# heater_controller.net
KiCad netlist of a schematic drawn in EAGLE
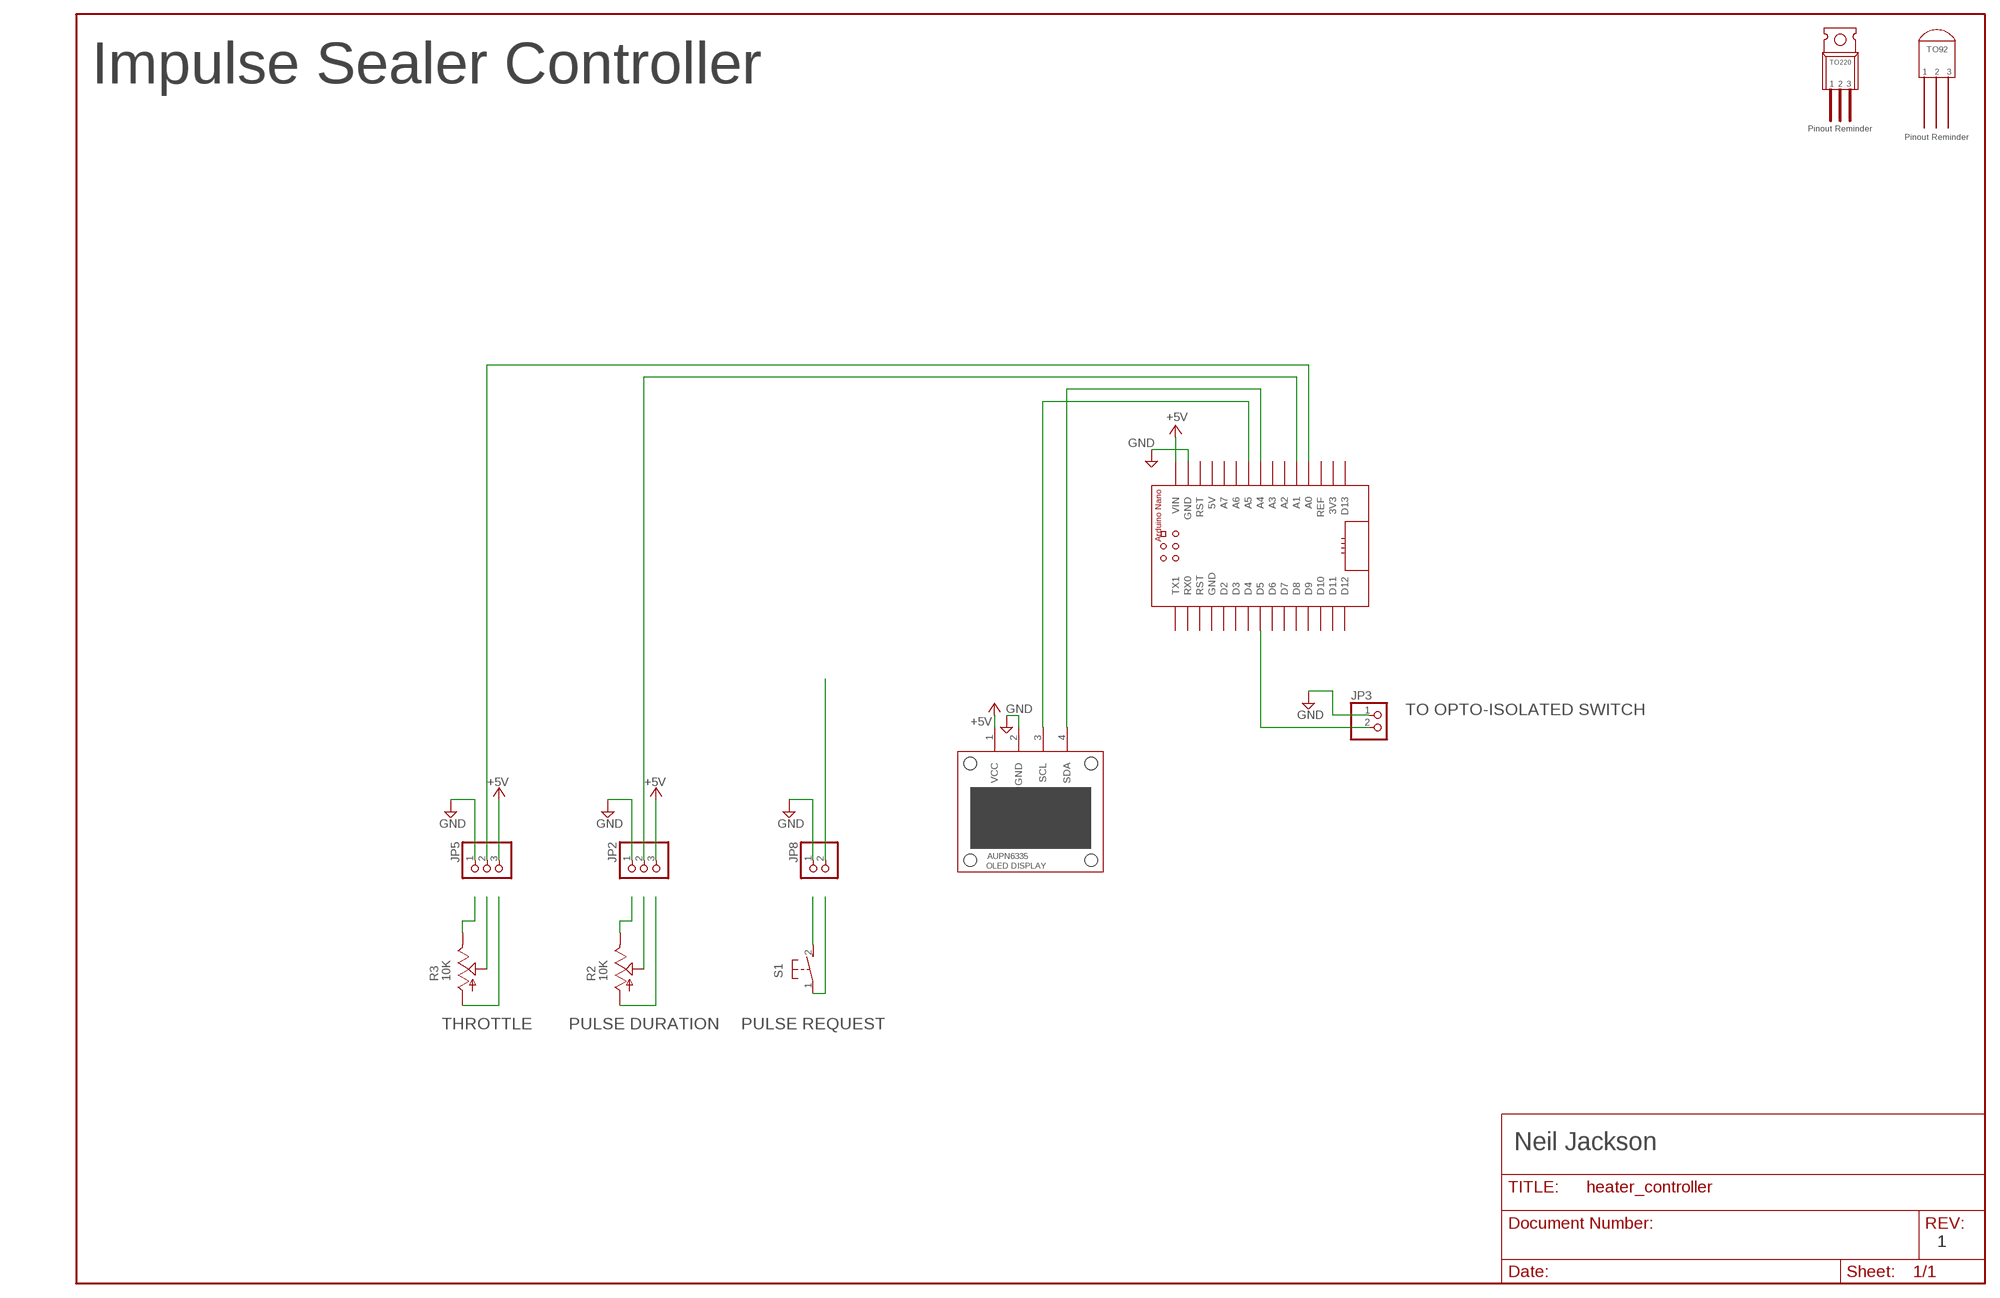
[diagram p0: schematic, sheet 1]

(export (version "E")
  (design (tool "Eeschema 10.0.6"))
  (components
    (comp (ref "JP2")
      (value "PINHD-1X3")
      (footprint "eagle-import:1X03")
      (libsource (lib "eagle-import") (part "PINHD-1X3"))
    )
    (comp (ref "JP3")
      (value "PINHD-1X2")
      (footprint "eagle-import:1X02")
      (libsource (lib "eagle-import") (part "PINHD-1X2"))
    )
    (comp (ref "JP5")
      (value "PINHD-1X3")
      (footprint "eagle-import:1X03")
      (libsource (lib "eagle-import") (part "PINHD-1X3"))
    )
    (comp (ref "JP8")
      (value "PINHD-1X2")
      (footprint "eagle-import:1X02")
      (libsource (lib "eagle-import") (part "PINHD-1X2"))
    )
    (comp (ref "R2")
      (value "10K")
      (footprint "eagle-import:B64Y")
      (libsource (lib "eagle-import") (part "TRIM_US-B64Y"))
    )
    (comp (ref "R3")
      (value "10K")
      (footprint "eagle-import:B64Y")
      (libsource (lib "eagle-import") (part "TRIM_US-B64Y"))
    )
    (comp (ref "S1")
      (value "31-XX")
      (footprint "eagle-import:B3F-31XX")
      (fields (field (name "MPN") "B3F-3100"))
      (libsource (lib "eagle-import") (part "31-XX"))
    )
    (comp (ref "U$3")
      (value "AUPN6335")
      (footprint "eagle-import:AUPN6335")
      (libsource (lib "eagle-import") (part "AUPN6335"))
    )
    (comp (ref "U$5")
      (value "ARDUINO_NANO")
      (footprint "eagle-import:ARDUINO_NANO")
      (libsource (lib "eagle-import") (part "ARDUINO_NANO"))
    )
  )
  (nets
    (net (code "1") (name "+5V") (class "Default")
      (node (ref "JP2") (pin "3") (pinfunction "3_3") (pintype "passive"))
      (node (ref "JP5") (pin "3") (pinfunction "3_3") (pintype "passive"))
      (node (ref "U$3") (pin "1") (pinfunction "VCC_1") (pintype "input"))
      (node (ref "U$5") (pin "15") (pinfunction "VIN_15") (pintype "bidirectional"))
    )
    (net (code "2") (name "GND") (class "Default")
      (node (ref "JP2") (pin "1") (pinfunction "1_1") (pintype "passive"))
      (node (ref "JP3") (pin "1") (pinfunction "1_1") (pintype "passive"))
      (node (ref "JP5") (pin "1") (pinfunction "1_1") (pintype "passive"))
      (node (ref "JP8") (pin "1") (pinfunction "1_1") (pintype "passive"))
      (node (ref "U$3") (pin "2") (pinfunction "GND_2") (pintype "bidirectional"))
      (node (ref "U$5") (pin "14") (pinfunction "GND_14") (pintype "bidirectional"))
    )
    (net (code "3") (name "Net-(U$3-SCL)") (class "Default")
      (node (ref "U$3") (pin "3") (pinfunction "SCL_3") (pintype "bidirectional"))
      (node (ref "U$5") (pin "9") (pinfunction "A5_9") (pintype "bidirectional"))
    )
    (net (code "4") (name "Net-(U$3-SDA)") (class "Default")
      (node (ref "U$3") (pin "4") (pinfunction "SDA_4") (pintype "bidirectional"))
      (node (ref "U$5") (pin "8") (pinfunction "A4_8") (pintype "bidirectional"))
    )
    (net (code "5") (name "Net-(U$5-A0)") (class "Default")
      (node (ref "JP5") (pin "2") (pinfunction "2_2") (pintype "passive"))
      (node (ref "U$5") (pin "4") (pinfunction "A0_4") (pintype "bidirectional"))
    )
    (net (code "6") (name "Net-(U$5-A1)") (class "Default")
      (node (ref "JP2") (pin "2") (pinfunction "2_2") (pintype "passive"))
      (node (ref "U$5") (pin "5") (pinfunction "A1_5") (pintype "bidirectional"))
    )
    (net (code "7") (name "Net-(U$5-D5)") (class "Default")
      (node (ref "JP3") (pin "2") (pinfunction "2_2") (pintype "passive"))
      (node (ref "U$5") (pin "23") (pinfunction "D5_23") (pintype "bidirectional"))
    )
    (net (code "8") (name "unconnected-(JP8-Pad2)") (class "Default")
      (node (ref "JP8") (pin "2") (pinfunction "2_2") (pintype "passive"))
    )
    (net (code "9") (name "unconnected-(R2-PadA)") (class "Default")
      (node (ref "R2") (pin "A") (pinfunction "A_A") (pintype "passive"))
    )
    (net (code "10") (name "unconnected-(R2-PadE)") (class "Default")
      (node (ref "R2") (pin "E") (pinfunction "E_E") (pintype "passive"))
    )
    (net (code "11") (name "unconnected-(R2-PadS)") (class "Default")
      (node (ref "R2") (pin "S") (pinfunction "S_S") (pintype "passive"))
    )
    (net (code "12") (name "unconnected-(R3-PadA)") (class "Default")
      (node (ref "R3") (pin "A") (pinfunction "A_A") (pintype "passive"))
    )
    (net (code "13") (name "unconnected-(R3-PadE)") (class "Default")
      (node (ref "R3") (pin "E") (pinfunction "E_E") (pintype "passive"))
    )
    (net (code "14") (name "unconnected-(R3-PadS)") (class "Default")
      (node (ref "R3") (pin "S") (pinfunction "S_S") (pintype "passive"))
    )
    (net (code "15") (name "unconnected-(S1-P-Pad1)") (class "Default")
      (node (ref "S1") (pin "1") (pinfunction "P_1") (pintype "passive"))
    )
    (net (code "16") (name "unconnected-(S1-S-Pad2)") (class "Default")
      (node (ref "S1") (pin "2") (pinfunction "S_2") (pintype "passive"))
    )
    (net (code "17") (name "unconnected-(U$5-3V3-Pad2)") (class "Default")
      (node (ref "U$5") (pin "2") (pinfunction "3V3_2") (pintype "bidirectional"))
    )
    (net (code "18") (name "unconnected-(U$5-5V-Pad12)") (class "Default")
      (node (ref "U$5") (pin "12") (pinfunction "5V_12") (pintype "bidirectional"))
    )
    (net (code "19") (name "unconnected-(U$5-A2-Pad6)") (class "Default")
      (node (ref "U$5") (pin "6") (pinfunction "A2_6") (pintype "bidirectional"))
    )
    (net (code "20") (name "unconnected-(U$5-A3-Pad7)") (class "Default")
      (node (ref "U$5") (pin "7") (pinfunction "A3_7") (pintype "bidirectional"))
    )
    (net (code "21") (name "unconnected-(U$5-A6-Pad10)") (class "Default")
      (node (ref "U$5") (pin "10") (pinfunction "A6_10") (pintype "bidirectional"))
    )
    (net (code "22") (name "unconnected-(U$5-A7-Pad11)") (class "Default")
      (node (ref "U$5") (pin "11") (pinfunction "A7_11") (pintype "bidirectional"))
    )
    (net (code "23") (name "unconnected-(U$5-D2-Pad20)") (class "Default")
      (node (ref "U$5") (pin "20") (pinfunction "D2_20") (pintype "bidirectional"))
    )
    (net (code "24") (name "unconnected-(U$5-D3-Pad21)") (class "Default")
      (node (ref "U$5") (pin "21") (pinfunction "D3_21") (pintype "bidirectional"))
    )
    (net (code "25") (name "unconnected-(U$5-D4-Pad22)") (class "Default")
      (node (ref "U$5") (pin "22") (pinfunction "D4_22") (pintype "bidirectional"))
    )
    (net (code "26") (name "unconnected-(U$5-D6-Pad24)") (class "Default")
      (node (ref "U$5") (pin "24") (pinfunction "D6_24") (pintype "bidirectional"))
    )
    (net (code "27") (name "unconnected-(U$5-D7-Pad25)") (class "Default")
      (node (ref "U$5") (pin "25") (pinfunction "D7_25") (pintype "bidirectional"))
    )
    (net (code "28") (name "unconnected-(U$5-D8-Pad26)") (class "Default")
      (node (ref "U$5") (pin "26") (pinfunction "D8_26") (pintype "bidirectional"))
    )
    (net (code "29") (name "unconnected-(U$5-D9-Pad27)") (class "Default")
      (node (ref "U$5") (pin "27") (pinfunction "D9_27") (pintype "bidirectional"))
    )
    (net (code "30") (name "unconnected-(U$5-D10-Pad28)") (class "Default")
      (node (ref "U$5") (pin "28") (pinfunction "D10_28") (pintype "bidirectional"))
    )
    (net (code "31") (name "unconnected-(U$5-D11-Pad29)") (class "Default")
      (node (ref "U$5") (pin "29") (pinfunction "D11_29") (pintype "bidirectional"))
    )
    (net (code "32") (name "unconnected-(U$5-D12-Pad30)") (class "Default")
      (node (ref "U$5") (pin "30") (pinfunction "D12_30") (pintype "bidirectional"))
    )
    (net (code "33") (name "unconnected-(U$5-D13-Pad1)") (class "Default")
      (node (ref "U$5") (pin "1") (pinfunction "D13_1") (pintype "bidirectional"))
    )
    (net (code "34") (name "unconnected-(U$5-GND-Pad19)") (class "Default")
      (node (ref "U$5") (pin "19") (pinfunction "GND_19") (pintype "bidirectional"))
    )
    (net (code "35") (name "unconnected-(U$5-REF-Pad3)") (class "Default")
      (node (ref "U$5") (pin "3") (pinfunction "REF_3") (pintype "bidirectional"))
    )
    (net (code "36") (name "unconnected-(U$5-RST-Pad13)") (class "Default")
      (node (ref "U$5") (pin "13") (pinfunction "RST_13") (pintype "bidirectional"))
    )
    (net (code "37") (name "unconnected-(U$5-RST-Pad18)") (class "Default")
      (node (ref "U$5") (pin "18") (pinfunction "RST_18") (pintype "bidirectional"))
    )
    (net (code "38") (name "unconnected-(U$5-RX0-Pad17)") (class "Default")
      (node (ref "U$5") (pin "17") (pinfunction "RX0_17") (pintype "bidirectional"))
    )
    (net (code "39") (name "unconnected-(U$5-TX1-Pad16)") (class "Default")
      (node (ref "U$5") (pin "16") (pinfunction "TX1_16") (pintype "bidirectional"))
    )
  )
)
